# IMU_module.net
KiCad netlist of a schematic drawn in EAGLE
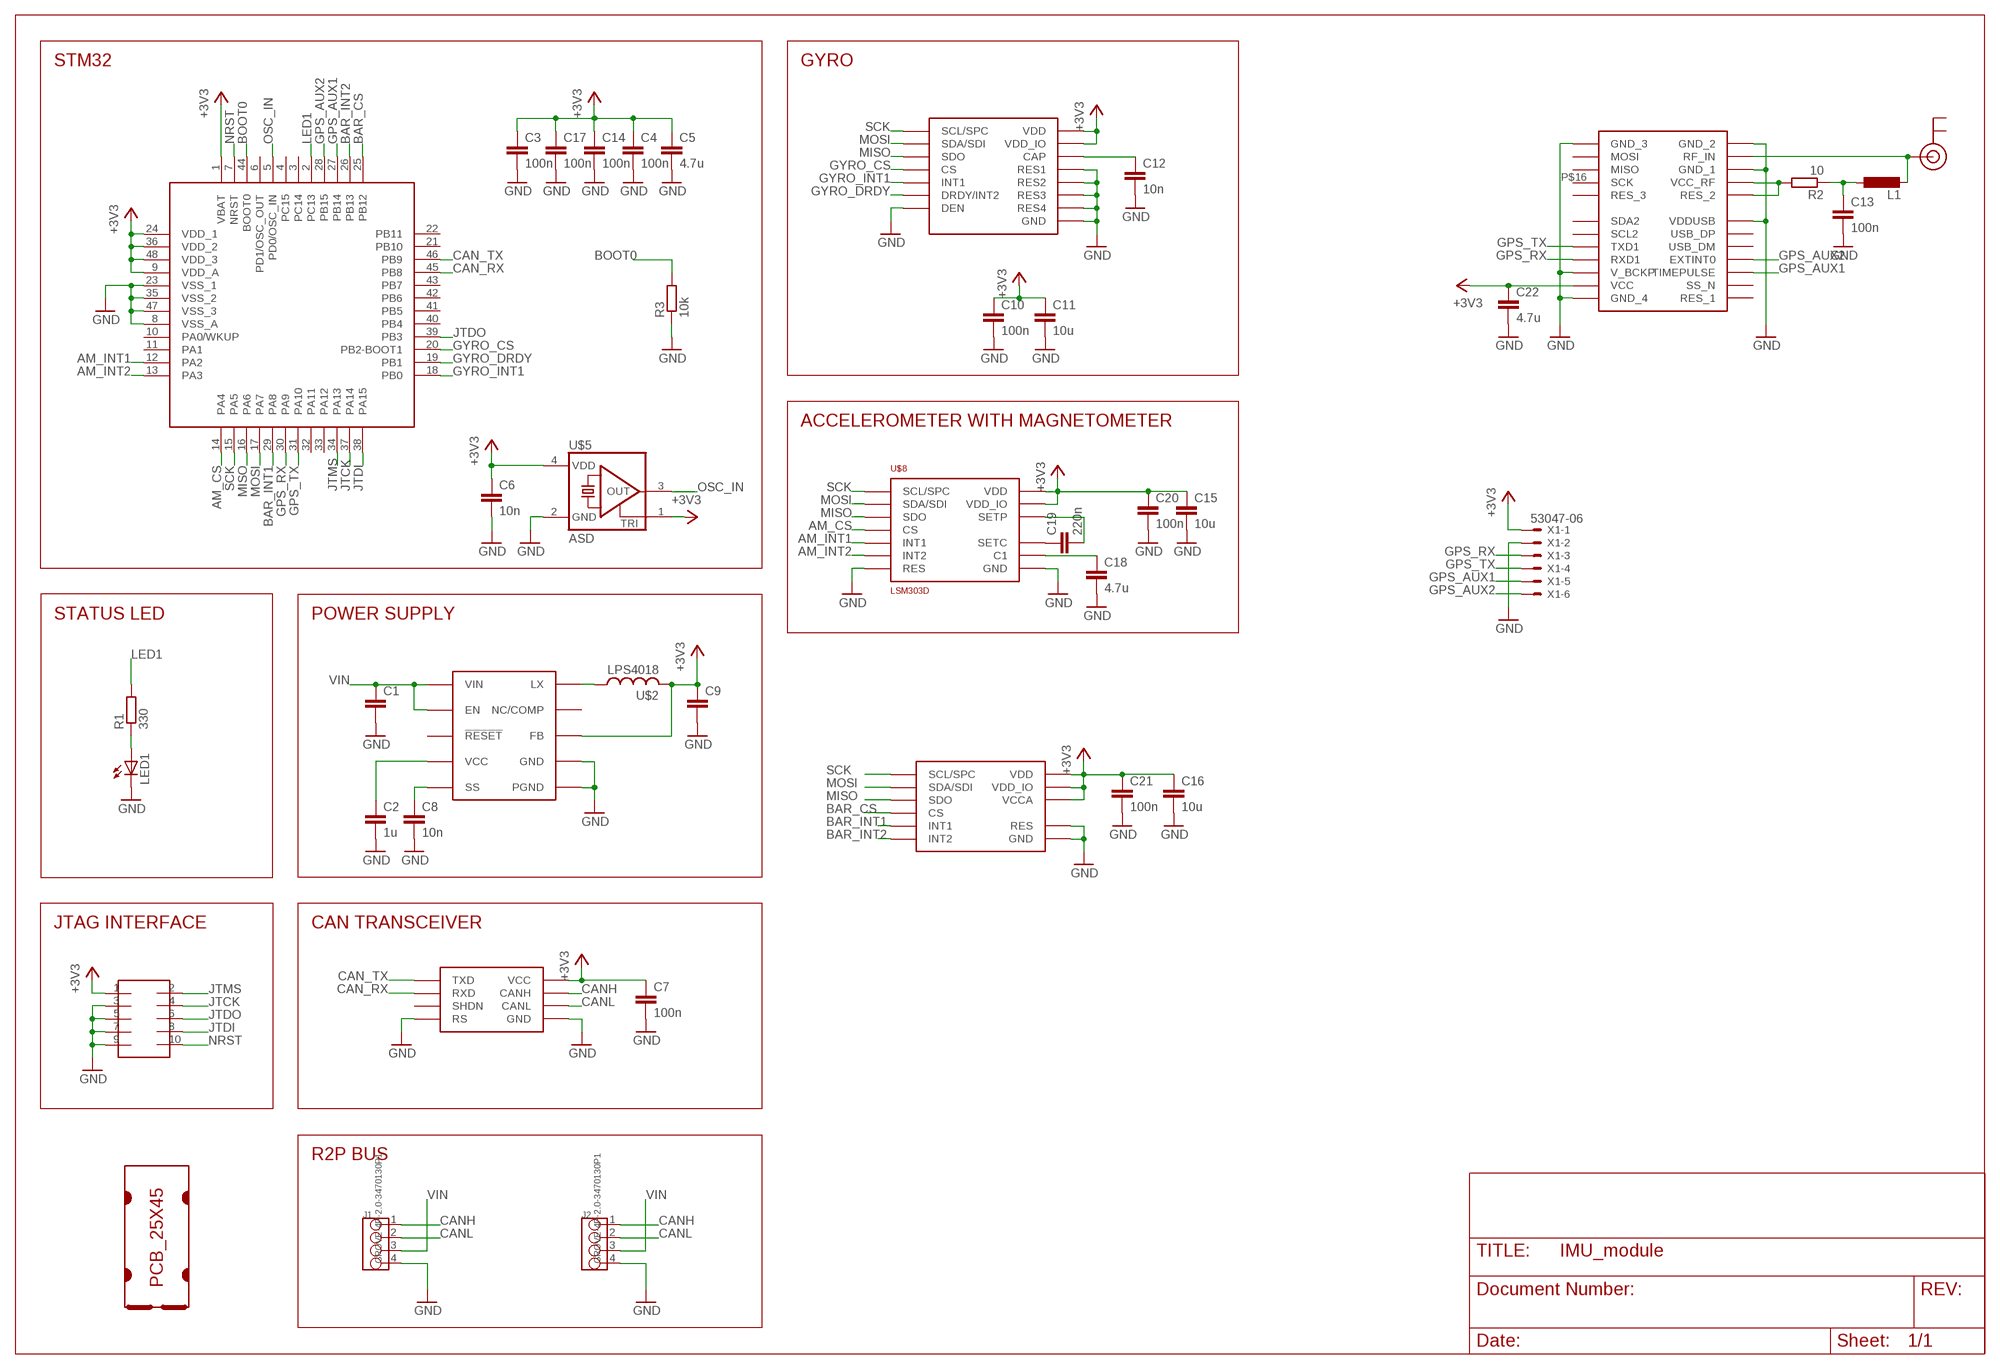
[diagram p0: schematic, sheet 1]

(export (version "E")
  (design (tool "Eeschema 10.0.6"))
  (components
    (comp (ref "C1")
      (value "C-EUC1206")
      (footprint "eagle-import:C1206")
      (libsource (lib "eagle-import") (part "C-EUC1206"))
    )
    (comp (ref "C2")
      (value "1u")
      (footprint "eagle-import:C0603")
      (libsource (lib "eagle-import") (part "C-EUC0603"))
    )
    (comp (ref "C3")
      (value "100n")
      (footprint "eagle-import:C0603")
      (libsource (lib "eagle-import") (part "C-EUC0603"))
    )
    (comp (ref "C4")
      (value "100n")
      (footprint "eagle-import:C0603")
      (libsource (lib "eagle-import") (part "C-EUC0603"))
    )
    (comp (ref "C5")
      (value "4.7u")
      (footprint "eagle-import:C0805")
      (libsource (lib "eagle-import") (part "C-EUC0805"))
    )
    (comp (ref "C6")
      (value "10n")
      (footprint "eagle-import:C0603")
      (libsource (lib "eagle-import") (part "C-EUC0603"))
    )
    (comp (ref "C7")
      (value "100n")
      (footprint "eagle-import:C0603")
      (libsource (lib "eagle-import") (part "C-EUC0603"))
    )
    (comp (ref "C8")
      (value "10n")
      (footprint "eagle-import:C0603")
      (libsource (lib "eagle-import") (part "C-EUC0603"))
    )
    (comp (ref "C9")
      (value "C-EUC0805")
      (footprint "eagle-import:C0805")
      (libsource (lib "eagle-import") (part "C-EUC0805"))
    )
    (comp (ref "C10")
      (value "100n")
      (footprint "eagle-import:C0603")
      (libsource (lib "eagle-import") (part "C-EUC0603"))
    )
    (comp (ref "C11")
      (value "10u")
      (footprint "eagle-import:C0805")
      (libsource (lib "eagle-import") (part "C-EUC0805"))
    )
    (comp (ref "C12")
      (value "10n")
      (footprint "eagle-import:C0603")
      (libsource (lib "eagle-import") (part "C-EUC0603"))
    )
    (comp (ref "C13")
      (value "100n")
      (footprint "eagle-import:C0603")
      (libsource (lib "eagle-import") (part "C-EUC0603"))
    )
    (comp (ref "C14")
      (value "100n")
      (footprint "eagle-import:C0603")
      (libsource (lib "eagle-import") (part "C-EUC0603"))
    )
    (comp (ref "C15")
      (value "10u")
      (footprint "eagle-import:C0805")
      (libsource (lib "eagle-import") (part "C-EUC0805"))
    )
    (comp (ref "C16")
      (value "10u")
      (footprint "eagle-import:C0805")
      (libsource (lib "eagle-import") (part "C-EUC0805"))
    )
    (comp (ref "C17")
      (value "100n")
      (footprint "eagle-import:C0603")
      (libsource (lib "eagle-import") (part "C-EUC0603"))
    )
    (comp (ref "C18")
      (value "4.7u")
      (footprint "eagle-import:C0805")
      (libsource (lib "eagle-import") (part "C-EUC0805"))
    )
    (comp (ref "C19")
      (value "220n")
      (footprint "eagle-import:C0603")
      (libsource (lib "eagle-import") (part "C-EUC0603"))
    )
    (comp (ref "C20")
      (value "100n")
      (footprint "eagle-import:C0603")
      (libsource (lib "eagle-import") (part "C-EUC0603"))
    )
    (comp (ref "C21")
      (value "100n")
      (footprint "eagle-import:C0603")
      (libsource (lib "eagle-import") (part "C-EUC0603"))
    )
    (comp (ref "C22")
      (value "4.7u")
      (footprint "eagle-import:C0805")
      (libsource (lib "eagle-import") (part "C-EUC0805"))
    )
    (comp (ref "J1")
      (value "GROVE-4P-2.0-3470130P1")
      (footprint "eagle-import:4P-2.0")
      (libsource (lib "eagle-import") (part "GROVE-4P-2.0-3470130P1"))
    )
    (comp (ref "J2")
      (value "GROVE-4P-2.0-3470130P1")
      (footprint "eagle-import:4P-2.0")
      (libsource (lib "eagle-import") (part "GROVE-4P-2.0-3470130P1"))
    )
    (comp (ref "L1")
      (value "L-EUL2012C")
      (footprint "eagle-import:L2012C")
      (libsource (lib "eagle-import") (part "L-EUL2012C"))
    )
    (comp (ref "LED1")
      (value "LEDCHIPLED_0805")
      (footprint "eagle-import:CHIPLED_0805")
      (libsource (lib "eagle-import") (part "LEDCHIPLED_0805"))
    )
    (comp (ref "R1")
      (value "330")
      (footprint "eagle-import:R0603")
      (libsource (lib "eagle-import") (part "R-EU_R0603"))
    )
    (comp (ref "R2")
      (value "10")
      (footprint "eagle-import:R0603")
      (libsource (lib "eagle-import") (part "R-EU_R0603"))
    )
    (comp (ref "R3")
      (value "10k")
      (footprint "eagle-import:R0603")
      (libsource (lib "eagle-import") (part "R-EU_R0603"))
    )
    (comp (ref "SOT1")
      (value "MAX3051EKA")
      (footprint "eagle-import:SOT23-8L")
      (libsource (lib "eagle-import") (part "MAX3051EKA"))
    )
    (comp (ref "U$1")
      (value "PCB_25X45")
      (footprint "eagle-import:25X45")
      (libsource (lib "eagle-import") (part "PCB_25X45"))
    )
    (comp (ref "U$2")
      (value "LPS4018")
      (footprint "eagle-import:LPS4018")
      (libsource (lib "eagle-import") (part "LPS4018"))
    )
    (comp (ref "U$3")
      (value "MAX17501")
      (footprint "eagle-import:TDFN-10")
      (libsource (lib "eagle-import") (part "MAX17501"))
    )
    (comp (ref "U$4")
      (value "FTSH-105TH")
      (footprint "eagle-import:FTSH-105-TH")
      (libsource (lib "eagle-import") (part "FTSH-105TH"))
    )
    (comp (ref "U$5")
      (value "ASD")
      (footprint "eagle-import:2.5X2")
      (libsource (lib "eagle-import") (part "ASD"))
    )
    (comp (ref "U$6")
      (value "STM32F103CXTX")
      (footprint "eagle-import:LQFP48")
      (libsource (lib "eagle-import") (part "STM32F103CXTX"))
    )
    (comp (ref "U$7")
      (value "L3GD20H")
      (footprint "eagle-import:LGA16L")
      (libsource (lib "eagle-import") (part "L3GD20H"))
    )
    (comp (ref "U$8")
      (value "LSM303D")
      (footprint "eagle-import:LGA16L")
      (libsource (lib "eagle-import") (part "LSM303D"))
    )
    (comp (ref "U$9")
      (value "LPS331AP")
      (footprint "eagle-import:LGA16L")
      (libsource (lib "eagle-import") (part "LPS331AP"))
    )
    (comp (ref "U$10")
      (value "NEO-6")
      (footprint "eagle-import:NEO")
      (libsource (lib "eagle-import") (part "NEO-6"))
    )
    (comp (ref "U$11")
      (value "U.FL")
      (footprint "eagle-import:U.FL")
      (libsource (lib "eagle-import") (part "U.FL"))
    )
    (comp (ref "X1")
      (value "53047-06")
      (footprint "eagle-import:53047-06")
      (fields (field (name "MPN") "53047-0610-C"))
      (libsource (lib "eagle-import") (part "53?-06047"))
    )
  )
  (nets
    (net (code "1") (name "+3V3") (class "Default")
      (node (ref "C10") (pin "1") (pinfunction "1_1") (pintype "passive"))
      (node (ref "C11") (pin "1") (pinfunction "1_1") (pintype "passive"))
      (node (ref "C14") (pin "1") (pinfunction "1_1") (pintype "passive"))
      (node (ref "C15") (pin "1") (pinfunction "1_1") (pintype "passive"))
      (node (ref "C16") (pin "1") (pinfunction "1_1") (pintype "passive"))
      (node (ref "C17") (pin "1") (pinfunction "1_1") (pintype "passive"))
      (node (ref "C20") (pin "1") (pinfunction "1_1") (pintype "passive"))
      (node (ref "C21") (pin "1") (pinfunction "1_1") (pintype "passive"))
      (node (ref "C22") (pin "1") (pinfunction "1_1") (pintype "passive"))
      (node (ref "C3") (pin "1") (pinfunction "1_1") (pintype "passive"))
      (node (ref "C4") (pin "1") (pinfunction "1_1") (pintype "passive"))
      (node (ref "C5") (pin "1") (pinfunction "1_1") (pintype "passive"))
      (node (ref "C6") (pin "1") (pinfunction "1_1") (pintype "passive"))
      (node (ref "C7") (pin "1") (pinfunction "1_1") (pintype "passive"))
      (node (ref "C9") (pin "1") (pinfunction "1_1") (pintype "passive"))
      (node (ref "SOT1") (pin "3") (pinfunction "VCC_3") (pintype "bidirectional"))
      (node (ref "U$10") (pin "P$23") (pinfunction "VCC_P$23") (pintype "bidirectional"))
      (node (ref "U$2") (pin "P$2") (pinfunction "2_P$2") (pintype "passive"))
      (node (ref "U$3") (pin "P$5") (pinfunction "FB_P$5") (pintype "bidirectional"))
      (node (ref "U$4") (pin "1") (pinfunction "P$1_1") (pintype "bidirectional"))
      (node (ref "U$5") (pin "1") (pinfunction "TRI_1") (pintype "input"))
      (node (ref "U$5") (pin "4") (pinfunction "VDD_4") (pintype "power_in"))
      (node (ref "U$6") (pin "1") (pinfunction "VBAT_1") (pintype "bidirectional"))
      (node (ref "U$6") (pin "24") (pinfunction "VDD_1_24") (pintype "bidirectional"))
      (node (ref "U$6") (pin "36") (pinfunction "VDD_2_36") (pintype "bidirectional"))
      (node (ref "U$6") (pin "48") (pinfunction "VDD_3_48") (pintype "bidirectional"))
      (node (ref "U$6") (pin "9") (pinfunction "VDD_A_9") (pintype "bidirectional"))
      (node (ref "U$7") (pin "P$1") (pinfunction "VDD_IO_P$1") (pintype "power_in"))
      (node (ref "U$7") (pin "P$16") (pinfunction "VDD_P$16") (pintype "power_in"))
      (node (ref "U$8") (pin "P$1") (pinfunction "VDD_IO_P$1") (pintype "power_in"))
      (node (ref "U$8") (pin "P$14") (pinfunction "VDD_P$14") (pintype "power_in"))
      (node (ref "U$9") (pin "P$1") (pinfunction "VDD_IO_P$1") (pintype "bidirectional"))
      (node (ref "U$9") (pin "P$14") (pinfunction "VDD_P$14") (pintype "bidirectional"))
      (node (ref "U$9") (pin "P$15") (pinfunction "VCCA_P$15") (pintype "bidirectional"))
      (node (ref "X1") (pin "1") (pinfunction "S_1") (pintype "passive"))
    )
    (net (code "2") (name "/AM_CS") (class "Default")
      (node (ref "U$6") (pin "14") (pinfunction "PA4_14") (pintype "bidirectional"))
      (node (ref "U$8") (pin "P$8") (pinfunction "CS_P$8") (pintype "bidirectional"))
    )
    (net (code "3") (name "/AM_INT1") (class "Default")
      (node (ref "U$6") (pin "12") (pinfunction "PA2_12") (pintype "bidirectional"))
      (node (ref "U$8") (pin "P$11") (pinfunction "INT1_P$11") (pintype "bidirectional"))
    )
    (net (code "4") (name "/AM_INT2") (class "Default")
      (node (ref "U$6") (pin "13") (pinfunction "PA3_13") (pintype "bidirectional"))
      (node (ref "U$8") (pin "P$9") (pinfunction "INT2_P$9") (pintype "bidirectional"))
    )
    (net (code "5") (name "/BAR_CS") (class "Default")
      (node (ref "U$6") (pin "25") (pinfunction "PB12_25") (pintype "bidirectional"))
      (node (ref "U$9") (pin "P$8") (pinfunction "CS_P$8") (pintype "bidirectional"))
    )
    (net (code "6") (name "/BAR_INT1") (class "Default")
      (node (ref "U$6") (pin "29") (pinfunction "PA8_29") (pintype "bidirectional"))
      (node (ref "U$9") (pin "P$11") (pinfunction "INT1_P$11") (pintype "bidirectional"))
    )
    (net (code "7") (name "/BAR_INT2") (class "Default")
      (node (ref "U$6") (pin "26") (pinfunction "PB13_26") (pintype "bidirectional"))
      (node (ref "U$9") (pin "P$9") (pinfunction "INT2_P$9") (pintype "bidirectional"))
    )
    (net (code "8") (name "/BOOT0") (class "Default")
      (node (ref "R3") (pin "2") (pinfunction "2_2") (pintype "passive"))
      (node (ref "U$6") (pin "44") (pinfunction "BOOT0_44") (pintype "bidirectional"))
    )
    (net (code "9") (name "/CANH") (class "Default")
      (node (ref "J1") (pin "1") (pinfunction "1_1") (pintype "bidirectional"))
      (node (ref "J2") (pin "1") (pinfunction "1_1") (pintype "bidirectional"))
      (node (ref "SOT1") (pin "7") (pinfunction "CANH_7") (pintype "bidirectional"))
    )
    (net (code "10") (name "/CANL") (class "Default")
      (node (ref "J1") (pin "2") (pinfunction "2_2") (pintype "bidirectional"))
      (node (ref "J2") (pin "2") (pinfunction "2_2") (pintype "bidirectional"))
      (node (ref "SOT1") (pin "6") (pinfunction "CANL_6") (pintype "bidirectional"))
    )
    (net (code "11") (name "/CAN_RX") (class "Default")
      (node (ref "SOT1") (pin "4") (pinfunction "RXD_4") (pintype "bidirectional"))
      (node (ref "U$6") (pin "45") (pinfunction "PB8_45") (pintype "bidirectional"))
    )
    (net (code "12") (name "/CAN_TX") (class "Default")
      (node (ref "SOT1") (pin "1") (pinfunction "TXD_1") (pintype "bidirectional"))
      (node (ref "U$6") (pin "46") (pinfunction "PB9_46") (pintype "bidirectional"))
    )
    (net (code "13") (name "/GPS_AUX1") (class "Default")
      (node (ref "U$10") (pin "P$3") (pinfunction "TIMEPULSE_P$3") (pintype "bidirectional"))
      (node (ref "U$6") (pin "27") (pinfunction "PB14_27") (pintype "bidirectional"))
      (node (ref "X1") (pin "5") (pinfunction "S_5") (pintype "passive"))
    )
    (net (code "14") (name "/GPS_AUX2") (class "Default")
      (node (ref "U$10") (pin "P$4") (pinfunction "EXTINT0_P$4") (pintype "bidirectional"))
      (node (ref "U$6") (pin "28") (pinfunction "PB15_28") (pintype "bidirectional"))
      (node (ref "X1") (pin "6") (pinfunction "S_6") (pintype "passive"))
    )
    (net (code "15") (name "/GPS_RX") (class "Default")
      (node (ref "U$10") (pin "P$21") (pinfunction "RXD1_P$21") (pintype "bidirectional"))
      (node (ref "U$6") (pin "30") (pinfunction "PA9_30") (pintype "bidirectional"))
      (node (ref "X1") (pin "3") (pinfunction "S_3") (pintype "passive"))
    )
    (net (code "16") (name "/GPS_TX") (class "Default")
      (node (ref "U$10") (pin "P$20") (pinfunction "TXD1_P$20") (pintype "bidirectional"))
      (node (ref "U$6") (pin "31") (pinfunction "PA10_31") (pintype "bidirectional"))
      (node (ref "X1") (pin "4") (pinfunction "S_4") (pintype "passive"))
    )
    (net (code "17") (name "/GYRO_CS") (class "Default")
      (node (ref "U$6") (pin "20") (pinfunction "PB2-BOOT1_20") (pintype "bidirectional"))
      (node (ref "U$7") (pin "P$5") (pinfunction "CS_P$5") (pintype "bidirectional"))
    )
    (net (code "18") (name "/GYRO_DRDY") (class "Default")
      (node (ref "U$6") (pin "19") (pinfunction "PB1_19") (pintype "bidirectional"))
      (node (ref "U$7") (pin "P$6") (pinfunction "DRDY/INT2_P$6") (pintype "bidirectional"))
    )
    (net (code "19") (name "/GYRO_INT1") (class "Default")
      (node (ref "U$6") (pin "18") (pinfunction "PB0_18") (pintype "bidirectional"))
      (node (ref "U$7") (pin "P$7") (pinfunction "INT1_P$7") (pintype "bidirectional"))
    )
    (net (code "20") (name "/JTCK") (class "Default")
      (node (ref "U$4") (pin "4") (pinfunction "P$4_4") (pintype "bidirectional"))
      (node (ref "U$6") (pin "37") (pinfunction "PA14_37") (pintype "bidirectional"))
    )
    (net (code "21") (name "/JTDI") (class "Default")
      (node (ref "U$4") (pin "8") (pinfunction "P$8_8") (pintype "bidirectional"))
      (node (ref "U$6") (pin "38") (pinfunction "PA15_38") (pintype "bidirectional"))
    )
    (net (code "22") (name "/JTDO") (class "Default")
      (node (ref "U$4") (pin "6") (pinfunction "P$6_6") (pintype "bidirectional"))
      (node (ref "U$6") (pin "39") (pinfunction "PB3_39") (pintype "bidirectional"))
    )
    (net (code "23") (name "/JTMS") (class "Default")
      (node (ref "U$4") (pin "2") (pinfunction "P$2_2") (pintype "bidirectional"))
      (node (ref "U$6") (pin "34") (pinfunction "PA13_34") (pintype "bidirectional"))
    )
    (net (code "24") (name "/LED1") (class "Default")
      (node (ref "R1") (pin "2") (pinfunction "2_2") (pintype "passive"))
      (node (ref "U$6") (pin "2") (pinfunction "PC13_2") (pintype "bidirectional"))
    )
    (net (code "25") (name "/MISO") (class "Default")
      (node (ref "U$6") (pin "16") (pinfunction "PA6_16") (pintype "bidirectional"))
      (node (ref "U$7") (pin "P$4") (pinfunction "SDO_P$4") (pintype "bidirectional"))
      (node (ref "U$8") (pin "P$7") (pinfunction "SDO_P$7") (pintype "bidirectional"))
      (node (ref "U$9") (pin "P$7") (pinfunction "SDO_P$7") (pintype "bidirectional"))
    )
    (net (code "26") (name "/MOSI") (class "Default")
      (node (ref "U$6") (pin "17") (pinfunction "PA7_17") (pintype "bidirectional"))
      (node (ref "U$7") (pin "P$3") (pinfunction "SDA/SDI_P$3") (pintype "bidirectional"))
      (node (ref "U$8") (pin "P$6") (pinfunction "SDA/SDI_P$6") (pintype "bidirectional"))
      (node (ref "U$9") (pin "P$6") (pinfunction "SDA/SDI_P$6") (pintype "bidirectional"))
    )
    (net (code "27") (name "/NRST") (class "Default")
      (node (ref "U$4") (pin "10") (pinfunction "P$10_10") (pintype "bidirectional"))
      (node (ref "U$6") (pin "7") (pinfunction "NRST_7") (pintype "bidirectional"))
    )
    (net (code "28") (name "/OSC_IN") (class "Default")
      (node (ref "U$5") (pin "3") (pinfunction "OUT_3") (pintype "output"))
      (node (ref "U$6") (pin "5") (pinfunction "PD0/OSC_IN_5") (pintype "bidirectional"))
    )
    (net (code "29") (name "/SCK") (class "Default")
      (node (ref "U$6") (pin "15") (pinfunction "PA5_15") (pintype "bidirectional"))
      (node (ref "U$7") (pin "P$2") (pinfunction "SCL/SPC_P$2") (pintype "bidirectional"))
      (node (ref "U$8") (pin "P$4") (pinfunction "SCL/SPC_P$4") (pintype "bidirectional"))
      (node (ref "U$9") (pin "P$4") (pinfunction "SCL/SPC_P$4") (pintype "bidirectional"))
    )
    (net (code "30") (name "/VIN") (class "Default")
      (node (ref "C1") (pin "1") (pinfunction "1_1") (pintype "passive"))
      (node (ref "J1") (pin "3") (pinfunction "3_3") (pintype "bidirectional"))
      (node (ref "J2") (pin "3") (pinfunction "3_3") (pintype "bidirectional"))
      (node (ref "U$3") (pin "P$2") (pinfunction "VIN_P$2") (pintype "bidirectional"))
      (node (ref "U$3") (pin "P$3") (pinfunction "EN_P$3") (pintype "bidirectional"))
    )
    (net (code "31") (name "GND") (class "Default")
      (node (ref "C1") (pin "2") (pinfunction "2_2") (pintype "passive"))
      (node (ref "C10") (pin "2") (pinfunction "2_2") (pintype "passive"))
      (node (ref "C11") (pin "2") (pinfunction "2_2") (pintype "passive"))
      (node (ref "C12") (pin "2") (pinfunction "2_2") (pintype "passive"))
      (node (ref "C13") (pin "2") (pinfunction "2_2") (pintype "passive"))
      (node (ref "C14") (pin "2") (pinfunction "2_2") (pintype "passive"))
      (node (ref "C15") (pin "2") (pinfunction "2_2") (pintype "passive"))
      (node (ref "C16") (pin "2") (pinfunction "2_2") (pintype "passive"))
      (node (ref "C17") (pin "2") (pinfunction "2_2") (pintype "passive"))
      (node (ref "C18") (pin "2") (pinfunction "2_2") (pintype "passive"))
      (node (ref "C2") (pin "2") (pinfunction "2_2") (pintype "passive"))
      (node (ref "C20") (pin "2") (pinfunction "2_2") (pintype "passive"))
      (node (ref "C21") (pin "2") (pinfunction "2_2") (pintype "passive"))
      (node (ref "C22") (pin "2") (pinfunction "2_2") (pintype "passive"))
      (node (ref "C3") (pin "2") (pinfunction "2_2") (pintype "passive"))
      (node (ref "C4") (pin "2") (pinfunction "2_2") (pintype "passive"))
      (node (ref "C5") (pin "2") (pinfunction "2_2") (pintype "passive"))
      (node (ref "C6") (pin "2") (pinfunction "2_2") (pintype "passive"))
      (node (ref "C7") (pin "2") (pinfunction "2_2") (pintype "passive"))
      (node (ref "C8") (pin "2") (pinfunction "2_2") (pintype "passive"))
      (node (ref "C9") (pin "2") (pinfunction "2_2") (pintype "passive"))
      (node (ref "J1") (pin "4") (pinfunction "4_4") (pintype "bidirectional"))
      (node (ref "J2") (pin "4") (pinfunction "4_4") (pintype "bidirectional"))
      (node (ref "LED1") (pin "C") (pinfunction "C_C") (pintype "passive"))
      (node (ref "R3") (pin "1") (pinfunction "1_1") (pintype "passive"))
      (node (ref "SOT1") (pin "2") (pinfunction "GND_2") (pintype "bidirectional"))
      (node (ref "SOT1") (pin "8") (pinfunction "RS_8") (pintype "bidirectional"))
      (node (ref "U$10") (pin "P$10") (pinfunction "GND_1_P$10") (pintype "bidirectional"))
      (node (ref "U$10") (pin "P$12") (pinfunction "GND_2_P$12") (pintype "bidirectional"))
      (node (ref "U$10") (pin "P$13") (pinfunction "GND_3_P$13") (pintype "bidirectional"))
      (node (ref "U$10") (pin "P$22") (pinfunction "V_BCKP_P$22") (pintype "bidirectional"))
      (node (ref "U$10") (pin "P$24") (pinfunction "GND_4_P$24") (pintype "bidirectional"))
      (node (ref "U$10") (pin "P$7") (pinfunction "VDDUSB_P$7") (pintype "bidirectional"))
      (node (ref "U$3") (pin "P$1") (pinfunction "PGND_P$1") (pintype "bidirectional"))
      (node (ref "U$3") (pin "P$11") (pinfunction "PGND_P$11") (pintype "bidirectional"))
      (node (ref "U$3") (pin "P$9") (pinfunction "GND_P$9") (pintype "bidirectional"))
      (node (ref "U$4") (pin "3") (pinfunction "P$3_3") (pintype "bidirectional"))
      (node (ref "U$4") (pin "5") (pinfunction "P$5_5") (pintype "bidirectional"))
      (node (ref "U$4") (pin "7") (pinfunction "P$7_7") (pintype "bidirectional"))
      (node (ref "U$4") (pin "9") (pinfunction "P$9_9") (pintype "bidirectional"))
      (node (ref "U$5") (pin "2") (pinfunction "GND_2") (pintype "power_in"))
      (node (ref "U$6") (pin "23") (pinfunction "VSS_1_23") (pintype "bidirectional"))
      (node (ref "U$6") (pin "35") (pinfunction "VSS_2_35") (pintype "bidirectional"))
      (node (ref "U$6") (pin "47") (pinfunction "VSS_3_47") (pintype "bidirectional"))
      (node (ref "U$6") (pin "8") (pinfunction "VSS_A_8") (pintype "bidirectional"))
      (node (ref "U$7") (pin "P$10") (pinfunction "RES2_P$10") (pintype "bidirectional"))
      (node (ref "U$7") (pin "P$11") (pinfunction "RES3_P$11") (pintype "bidirectional"))
      (node (ref "U$7") (pin "P$12") (pinfunction "GND_P$12") (pintype "power_in"))
      (node (ref "U$7") (pin "P$13") (pinfunction "GND_P$13") (pintype "power_in"))
      (node (ref "U$7") (pin "P$15") (pinfunction "RES4_P$15") (pintype "bidirectional"))
      (node (ref "U$7") (pin "P$8") (pinfunction "DEN_P$8") (pintype "bidirectional"))
      (node (ref "U$7") (pin "P$9") (pinfunction "RES1_P$9") (pintype "bidirectional"))
      (node (ref "U$8") (pin "P$10") (pinfunction "RES_P$10") (pintype "bidirectional"))
      (node (ref "U$8") (pin "P$12") (pinfunction "GND_P$12") (pintype "power_in"))
      (node (ref "U$8") (pin "P$13") (pinfunction "GND_P$13") (pintype "power_in"))
      (node (ref "U$8") (pin "P$16") (pinfunction "GND_P$16") (pintype "power_in"))
      (node (ref "U$8") (pin "P$5") (pinfunction "GND_P$5") (pintype "power_in"))
      (node (ref "U$9") (pin "P$10") (pinfunction "RES_P$10") (pintype "bidirectional"))
      (node (ref "U$9") (pin "P$12") (pinfunction "GND_P$12") (pintype "bidirectional"))
      (node (ref "U$9") (pin "P$13") (pinfunction "GND_P$13") (pintype "bidirectional"))
      (node (ref "U$9") (pin "P$16") (pinfunction "GND_P$16") (pintype "bidirectional"))
      (node (ref "U$9") (pin "P$5") (pinfunction "GND_P$5") (pintype "bidirectional"))
      (node (ref "X1") (pin "2") (pinfunction "S_2") (pintype "passive"))
    )
    (net (code "32") (name "Net-(C13-Pad1)") (class "Default")
      (node (ref "C13") (pin "1") (pinfunction "1_1") (pintype "passive"))
      (node (ref "L1") (pin "1") (pinfunction "1_1") (pintype "passive"))
      (node (ref "R2") (pin "1") (pinfunction "1_1") (pintype "passive"))
    )
    (net (code "33") (name "Net-(LED1-PadA)") (class "Default")
      (node (ref "LED1") (pin "A") (pinfunction "A_A") (pintype "passive"))
      (node (ref "R1") (pin "1") (pinfunction "1_1") (pintype "passive"))
    )
    (net (code "34") (name "Net-(U$2-1)") (class "Default")
      (node (ref "U$2") (pin "P$1") (pinfunction "1_P$1") (pintype "passive"))
      (node (ref "U$3") (pin "P$10") (pinfunction "LX_P$10") (pintype "bidirectional"))
    )
    (net (code "35") (name "Net-(U$3-SS)") (class "Default")
      (node (ref "C8") (pin "1") (pinfunction "1_1") (pintype "passive"))
      (node (ref "U$3") (pin "P$6") (pinfunction "SS_P$6") (pintype "bidirectional"))
    )
    (net (code "36") (name "Net-(U$3-VCC)") (class "Default")
      (node (ref "C2") (pin "1") (pinfunction "1_1") (pintype "passive"))
      (node (ref "U$3") (pin "P$4") (pinfunction "VCC_P$4") (pintype "bidirectional"))
    )
    (net (code "37") (name "Net-(U$7-CAP)") (class "Default")
      (node (ref "C12") (pin "1") (pinfunction "1_1") (pintype "passive"))
      (node (ref "U$7") (pin "P$14") (pinfunction "CAP_P$14") (pintype "bidirectional"))
    )
    (net (code "38") (name "Net-(U$8-C1)") (class "Default")
      (node (ref "C18") (pin "1") (pinfunction "1_1") (pintype "passive"))
      (node (ref "U$8") (pin "P$15") (pinfunction "C1_P$15") (pintype "bidirectional"))
    )
    (net (code "39") (name "Net-(U$8-SETC)") (class "Default")
      (node (ref "C19") (pin "1") (pinfunction "1_1") (pintype "passive"))
      (node (ref "U$8") (pin "P$2") (pinfunction "SETC_P$2") (pintype "bidirectional"))
    )
    (net (code "40") (name "Net-(U$8-SETP)") (class "Default")
      (node (ref "C19") (pin "2") (pinfunction "2_2") (pintype "passive"))
      (node (ref "U$8") (pin "P$3") (pinfunction "SETP_P$3") (pintype "bidirectional"))
    )
    (net (code "41") (name "Net-(U$10-RES_2)") (class "Default")
      (node (ref "R2") (pin "2") (pinfunction "2_2") (pintype "passive"))
      (node (ref "U$10") (pin "P$8") (pinfunction "RES_2_P$8") (pintype "bidirectional"))
      (node (ref "U$10") (pin "P$9") (pinfunction "VCC_RF_P$9") (pintype "bidirectional"))
    )
    (net (code "42") (name "Net-(U$10-RF_IN)") (class "Default")
      (node (ref "L1") (pin "2") (pinfunction "2_2") (pintype "passive"))
      (node (ref "U$10") (pin "P$11") (pinfunction "RF_IN_P$11") (pintype "bidirectional"))
      (node (ref "U$11") (pin "P$3") (pinfunction "SIGNAL_P$3") (pintype "bidirectional"))
    )
    (net (code "43") (name "unconnected-(SOT1-SHDN-Pad5)") (class "Default")
      (node (ref "SOT1") (pin "5") (pinfunction "SHDN_5") (pintype "bidirectional"))
    )
    (net (code "44") (name "unconnected-(U$3-NC{slash}COMP-PadP$7)") (class "Default")
      (node (ref "U$3") (pin "P$7") (pinfunction "NC/COMP_P$7") (pintype "bidirectional"))
    )
    (net (code "45") (name "unconnected-(U$3-~{RESET}-PadP$8)") (class "Default")
      (node (ref "U$3") (pin "P$8") (pinfunction "~{RESET}_P$8") (pintype "bidirectional"))
    )
    (net (code "46") (name "unconnected-(U$6-PA0{slash}WKUP-Pad10)") (class "Default")
      (node (ref "U$6") (pin "10") (pinfunction "PA0/WKUP_10") (pintype "bidirectional"))
    )
    (net (code "47") (name "unconnected-(U$6-PA1-Pad11)") (class "Default")
      (node (ref "U$6") (pin "11") (pinfunction "PA1_11") (pintype "bidirectional"))
    )
    (net (code "48") (name "unconnected-(U$6-PA11-Pad32)") (class "Default")
      (node (ref "U$6") (pin "32") (pinfunction "PA11_32") (pintype "bidirectional"))
    )
    (net (code "49") (name "unconnected-(U$6-PA12-Pad33)") (class "Default")
      (node (ref "U$6") (pin "33") (pinfunction "PA12_33") (pintype "bidirectional"))
    )
    (net (code "50") (name "unconnected-(U$6-PB4-Pad40)") (class "Default")
      (node (ref "U$6") (pin "40") (pinfunction "PB4_40") (pintype "bidirectional"))
    )
    (net (code "51") (name "unconnected-(U$6-PB5-Pad41)") (class "Default")
      (node (ref "U$6") (pin "41") (pinfunction "PB5_41") (pintype "bidirectional"))
    )
    (net (code "52") (name "unconnected-(U$6-PB6-Pad42)") (class "Default")
      (node (ref "U$6") (pin "42") (pinfunction "PB6_42") (pintype "bidirectional"))
    )
    (net (code "53") (name "unconnected-(U$6-PB7-Pad43)") (class "Default")
      (node (ref "U$6") (pin "43") (pinfunction "PB7_43") (pintype "bidirectional"))
    )
    (net (code "54") (name "unconnected-(U$6-PB10-Pad21)") (class "Default")
      (node (ref "U$6") (pin "21") (pinfunction "PB10_21") (pintype "bidirectional"))
    )
    (net (code "55") (name "unconnected-(U$6-PB11-Pad22)") (class "Default")
      (node (ref "U$6") (pin "22") (pinfunction "PB11_22") (pintype "bidirectional"))
    )
    (net (code "56") (name "unconnected-(U$6-PC14-Pad3)") (class "Default")
      (node (ref "U$6") (pin "3") (pinfunction "PC14_3") (pintype "bidirectional"))
    )
    (net (code "57") (name "unconnected-(U$6-PC15-Pad4)") (class "Default")
      (node (ref "U$6") (pin "4") (pinfunction "PC15_4") (pintype "bidirectional"))
    )
    (net (code "58") (name "unconnected-(U$6-PD1{slash}OSC_OUT-Pad6)") (class "Default")
      (node (ref "U$6") (pin "6") (pinfunction "PD1/OSC_OUT_6") (pintype "bidirectional"))
    )
    (net (code "59") (name "unconnected-(U$10-MISO-PadP$15)") (class "Default")
      (node (ref "U$10") (pin "P$15") (pinfunction "MISO_P$15") (pintype "bidirectional"))
    )
    (net (code "60") (name "unconnected-(U$10-MOSI-PadP$14)") (class "Default")
      (node (ref "U$10") (pin "P$14") (pinfunction "MOSI_P$14") (pintype "bidirectional"))
    )
    (net (code "61") (name "unconnected-(U$10-RES_1-PadP$1)") (class "Default")
      (node (ref "U$10") (pin "P$1") (pinfunction "RES_1_P$1") (pintype "bidirectional"))
    )
    (net (code "62") (name "unconnected-(U$10-RES_3-PadP$17)") (class "Default")
      (node (ref "U$10") (pin "P$17") (pinfunction "RES_3_P$17") (pintype "bidirectional"))
    )
    (net (code "63") (name "unconnected-(U$10-SCK-PadP$16)") (class "Default")
      (node (ref "U$10") (pin "P$16") (pinfunction "SCK_P$16") (pintype "bidirectional"))
    )
    (net (code "64") (name "unconnected-(U$10-SCL2-PadP$19)") (class "Default")
      (node (ref "U$10") (pin "P$19") (pinfunction "SCL2_P$19") (pintype "bidirectional"))
    )
    (net (code "65") (name "unconnected-(U$10-SDA2-PadP$18)") (class "Default")
      (node (ref "U$10") (pin "P$18") (pinfunction "SDA2_P$18") (pintype "bidirectional"))
    )
    (net (code "66") (name "unconnected-(U$10-SS_N-PadP$2)") (class "Default")
      (node (ref "U$10") (pin "P$2") (pinfunction "SS_N_P$2") (pintype "bidirectional"))
    )
    (net (code "67") (name "unconnected-(U$10-USB_DM-PadP$5)") (class "Default")
      (node (ref "U$10") (pin "P$5") (pinfunction "USB_DM_P$5") (pintype "bidirectional"))
    )
    (net (code "68") (name "unconnected-(U$10-USB_DP-PadP$6)") (class "Default")
      (node (ref "U$10") (pin "P$6") (pinfunction "USB_DP_P$6") (pintype "bidirectional"))
    )
    (net (code "69") (name "unconnected-(U$11-GND-PadP$1)") (class "Default")
      (node (ref "U$11") (pin "P$1") (pinfunction "GND_P$1") (pintype "bidirectional"))
    )
    (net (code "70") (name "unconnected-(U$11-GND-PadP$2)") (class "Default")
      (node (ref "U$11") (pin "P$2") (pinfunction "GND_P$2") (pintype "bidirectional"))
    )
  )
)
